# PCB-JOY-RCP_x.net
KiCad netlist of a schematic drawn in EAGLE
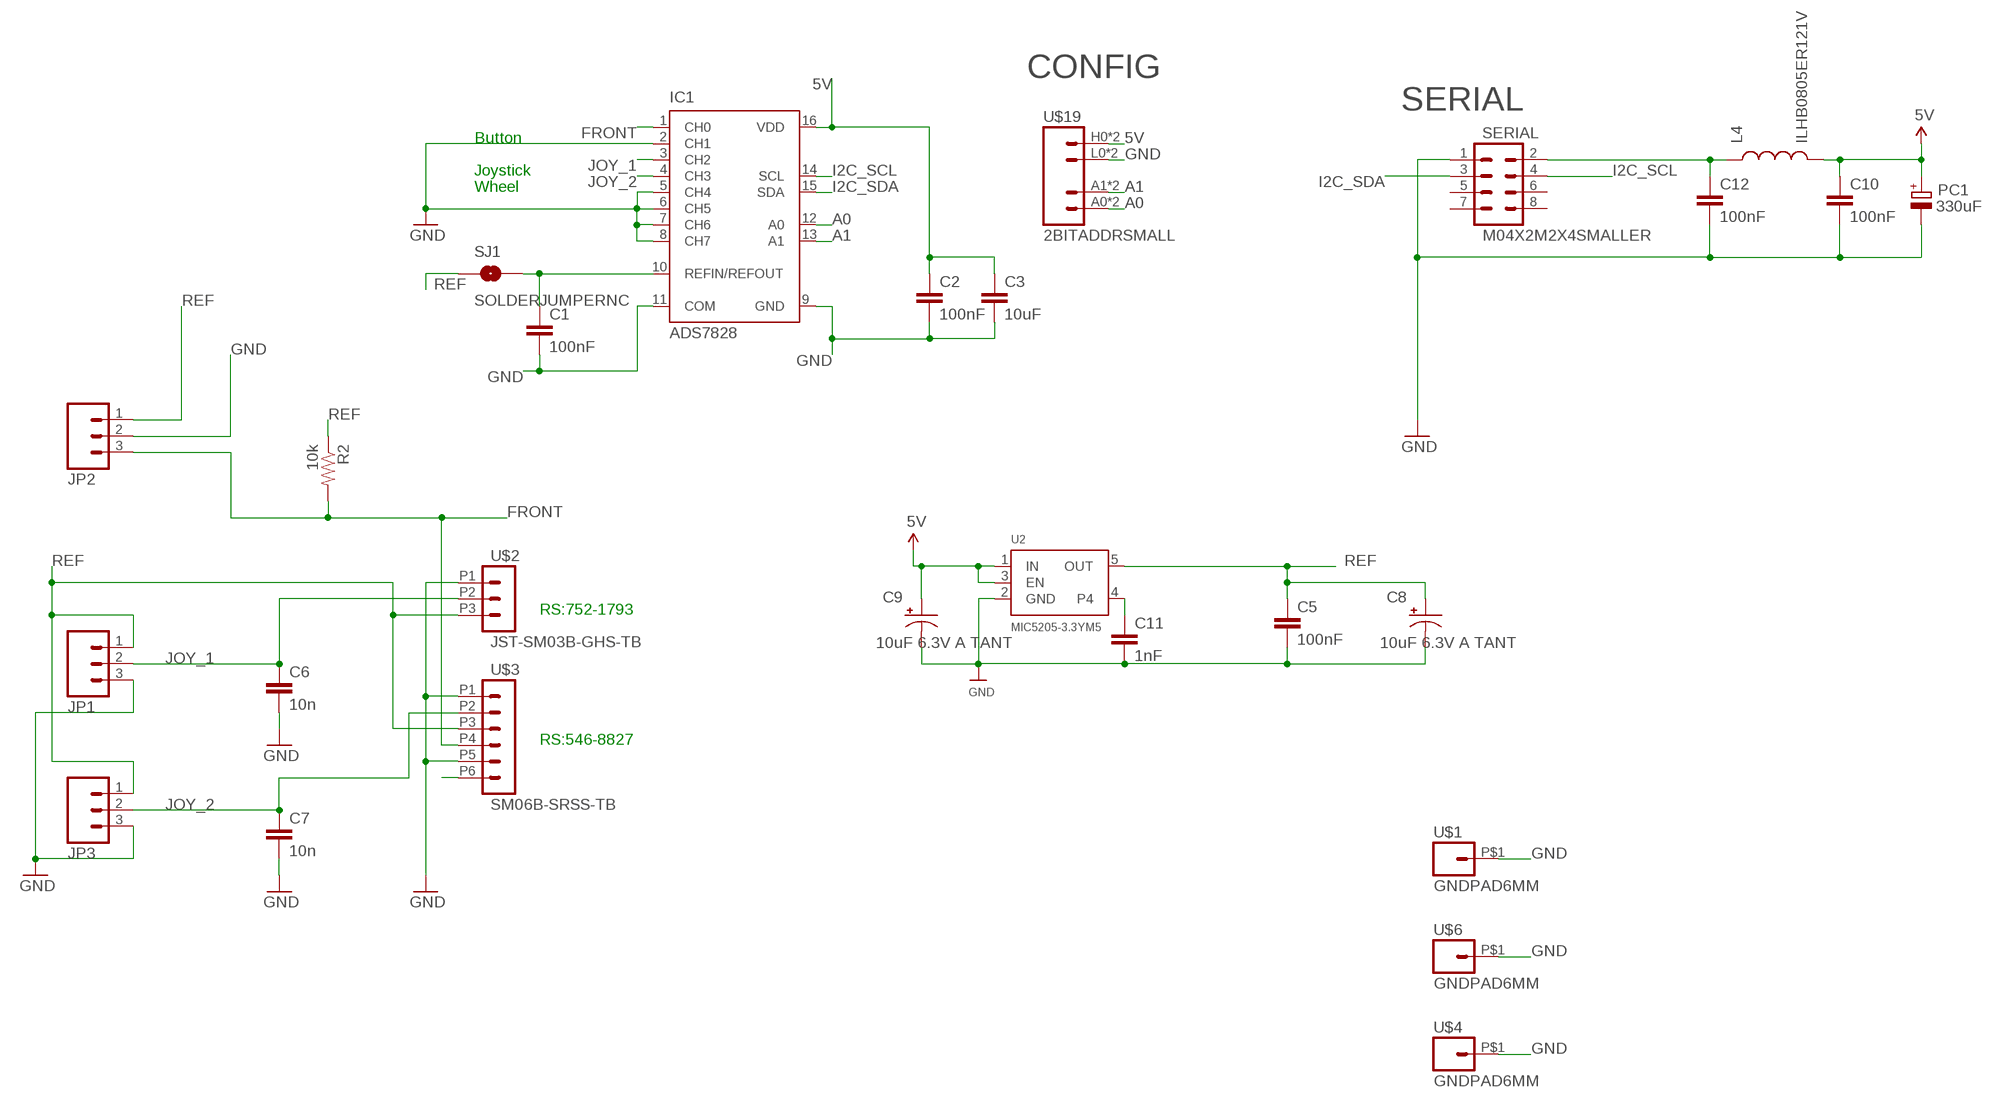
[diagram p0: schematic, sheet 1]

(export (version "E")
  (design (tool "Eeschema 10.0.6"))
  (components
    (comp (ref "C1")
      (value "100nF")
      (footprint "eagle-import:0603-CAP")
      (libsource (lib "eagle-import") (part "CAP0603-CAP"))
    )
    (comp (ref "C2")
      (value "100nF")
      (footprint "eagle-import:0603-CAP")
      (libsource (lib "eagle-import") (part "CAP0603-CAP"))
    )
    (comp (ref "C3")
      (value "10uF")
      (footprint "eagle-import:0805")
      (libsource (lib "eagle-import") (part "CAP0805"))
    )
    (comp (ref "C5")
      (value "100nF")
      (footprint "eagle-import:0603-CAP")
      (libsource (lib "eagle-import") (part "CAP0603-CAP"))
    )
    (comp (ref "C6")
      (value "10n")
      (footprint "eagle-import:0603-CAP")
      (libsource (lib "eagle-import") (part "CAP0603-CAP"))
    )
    (comp (ref "C7")
      (value "10n")
      (footprint "eagle-import:0603-CAP")
      (libsource (lib "eagle-import") (part "CAP0603-CAP"))
    )
    (comp (ref "C8")
      (value "10uF 6.3V A TANT")
      (footprint "eagle-import:EIA3216")
      (libsource (lib "eagle-import") (part "CAP_POL1206"))
    )
    (comp (ref "C9")
      (value "10uF 6.3V A TANT")
      (footprint "eagle-import:EIA3216")
      (libsource (lib "eagle-import") (part "CAP_POL1206"))
    )
    (comp (ref "C10")
      (value "100nF")
      (footprint "eagle-import:0603-CAP")
      (libsource (lib "eagle-import") (part "CAP0603-CAP"))
    )
    (comp (ref "C11")
      (value "1nF")
      (footprint "eagle-import:0603-CAP")
      (libsource (lib "eagle-import") (part "CAP0603-CAP"))
    )
    (comp (ref "C12")
      (value "100nF")
      (footprint "eagle-import:0603-CAP")
      (libsource (lib "eagle-import") (part "CAP0603-CAP"))
    )
    (comp (ref "IC1")
      (value "ADS7828")
      (footprint "eagle-import:TSSOP16-PW")
      (fields (field (name "MF") "TEXAS INSTRUMENTS") (field (name "MPN") "ADS7828E/250"))
      (libsource (lib "eagle-import") (part "ADS7828"))
    )
    (comp (ref "JP1")
      (value "M03PTH")
      (footprint "eagle-import:1X03")
      (libsource (lib "eagle-import") (part "M03PTH"))
    )
    (comp (ref "JP2")
      (value "M03PTH")
      (footprint "eagle-import:1X03")
      (libsource (lib "eagle-import") (part "M03PTH"))
    )
    (comp (ref "JP3")
      (value "M03PTH")
      (footprint "eagle-import:1X03")
      (libsource (lib "eagle-import") (part "M03PTH"))
    )
    (comp (ref "L4")
      (value "ILHB0805ER121V")
      (footprint "eagle-import:0805")
      (libsource (lib "eagle-import") (part "INDUCTOR0805"))
    )
    (comp (ref "PC1")
      (value "330uF")
      (footprint "eagle-import:PANASONIC_D")
      (libsource (lib "eagle-import") (part "CPOL-EUD"))
    )
    (comp (ref "R2")
      (value "10k")
      (footprint "eagle-import:0603-RES")
      (libsource (lib "eagle-import") (part "RESISTOR0603-RES"))
    )
    (comp (ref "SERIAL")
      (value "M04X2M2X4SMALLER")
      (footprint "eagle-import:M2X4SMALLER")
      (libsource (lib "eagle-import") (part "M04X2M2X4SMALLER"))
    )
    (comp (ref "SJ1")
      (value "SOLDERJUMPERNC")
      (footprint "eagle-import:SJ_2S")
      (libsource (lib "eagle-import") (part "SOLDERJUMPERNC"))
    )
    (comp (ref "U$1")
      (value "GNDPAD6MM")
      (footprint "eagle-import:3.2MMPAD6MM")
      (libsource (lib "eagle-import") (part "GNDPAD6MM"))
    )
    (comp (ref "U$2")
      (value "JST-SM03B-GHS-TB")
      (footprint "eagle-import:JST-SM03B-GHS-TB")
      (libsource (lib "eagle-import") (part "JST-SM03B-GHS-TB"))
    )
    (comp (ref "U$3")
      (value "SM06B-SRSS-TB")
      (footprint "eagle-import:JST-SM06B-SRSS-TB")
      (libsource (lib "eagle-import") (part "SM06B-SRSS-TB"))
    )
    (comp (ref "U$4")
      (value "GNDPAD6MM")
      (footprint "eagle-import:3.2MMPAD6MM")
      (libsource (lib "eagle-import") (part "GNDPAD6MM"))
    )
    (comp (ref "U$6")
      (value "GNDPAD6MM")
      (footprint "eagle-import:3.2MMPAD6MM")
      (libsource (lib "eagle-import") (part "GNDPAD6MM"))
    )
    (comp (ref "U$19")
      (value "2BITADDRSMALL")
      (footprint "eagle-import:2BITADDR_SMALL")
      (libsource (lib "eagle-import") (part "2BITADDRSMALL"))
    )
    (comp (ref "U2")
      (value "MIC5205-3.3YM5")
      (footprint "eagle-import:SOT23-5")
      (libsource (lib "eagle-import") (part "VREG_SOT23-5"))
    )
  )
  (nets
    (net (code "1") (name "/A0") (class "Default")
      (node (ref "IC1") (pin "12") (pinfunction "A0_12") (pintype "input"))
      (node (ref "U$19") (pin "A0") (pinfunction "A1_A0") (pintype "passive"))
      (node (ref "U$19") (pin "AS0") (pinfunction "A1_AS0") (pintype "passive"))
    )
    (net (code "2") (name "/A1") (class "Default")
      (node (ref "IC1") (pin "13") (pinfunction "A1_13") (pintype "input"))
      (node (ref "U$19") (pin "A1") (pinfunction "A2_A1") (pintype "passive"))
      (node (ref "U$19") (pin "AS1") (pinfunction "A2_AS1") (pintype "passive"))
    )
    (net (code "3") (name "/FRONT") (class "Default")
      (node (ref "IC1") (pin "1") (pinfunction "CH0_1") (pintype "input"))
      (node (ref "JP2") (pin "3") (pinfunction "3_3") (pintype "passive"))
      (node (ref "R2") (pin "2") (pinfunction "2_2") (pintype "passive"))
      (node (ref "U$3") (pin "P4") (pinfunction "4_P4") (pintype "passive"))
    )
    (net (code "4") (name "/I2C_SCL") (class "Default")
      (node (ref "IC1") (pin "14") (pinfunction "SCL_14") (pintype "input"))
      (node (ref "SERIAL") (pin "4") (pinfunction "4_4") (pintype "passive"))
    )
    (net (code "5") (name "/I2C_SDA") (class "Default")
      (node (ref "IC1") (pin "15") (pinfunction "SDA_15") (pintype "bidirectional"))
      (node (ref "SERIAL") (pin "3") (pinfunction "3_3") (pintype "passive"))
    )
    (net (code "6") (name "/JOY_1") (class "Default")
      (node (ref "C6") (pin "1") (pinfunction "1_1") (pintype "passive"))
      (node (ref "IC1") (pin "3") (pinfunction "CH2_3") (pintype "input"))
      (node (ref "JP1") (pin "2") (pinfunction "2_2") (pintype "passive"))
      (node (ref "U$2") (pin "P2") (pinfunction "2_P2") (pintype "passive"))
    )
    (net (code "7") (name "/JOY_2") (class "Default")
      (node (ref "C7") (pin "1") (pinfunction "1_1") (pintype "passive"))
      (node (ref "IC1") (pin "4") (pinfunction "CH3_4") (pintype "input"))
      (node (ref "JP3") (pin "2") (pinfunction "2_2") (pintype "passive"))
      (node (ref "U$3") (pin "P2") (pinfunction "2_P2") (pintype "passive"))
    )
    (net (code "8") (name "/REF") (class "Default")
      (node (ref "C5") (pin "1") (pinfunction "1_1") (pintype "passive"))
      (node (ref "C8") (pin "A") (pinfunction "+_A") (pintype "passive"))
      (node (ref "JP1") (pin "1") (pinfunction "1_1") (pintype "passive"))
      (node (ref "JP2") (pin "1") (pinfunction "1_1") (pintype "passive"))
      (node (ref "JP3") (pin "1") (pinfunction "1_1") (pintype "passive"))
      (node (ref "R2") (pin "1") (pinfunction "1_1") (pintype "passive"))
      (node (ref "SJ1") (pin "1") (pinfunction "1_1") (pintype "passive"))
      (node (ref "U$2") (pin "P3") (pinfunction "3_P3") (pintype "passive"))
      (node (ref "U$3") (pin "P3") (pinfunction "3_P3") (pintype "passive"))
      (node (ref "U2") (pin "5") (pinfunction "OUT_5") (pintype "bidirectional"))
    )
    (net (code "9") (name "5V") (class "Default")
      (node (ref "C10") (pin "1") (pinfunction "1_1") (pintype "passive"))
      (node (ref "C2") (pin "1") (pinfunction "1_1") (pintype "passive"))
      (node (ref "C3") (pin "1") (pinfunction "1_1") (pintype "passive"))
      (node (ref "C9") (pin "A") (pinfunction "+_A") (pintype "passive"))
      (node (ref "IC1") (pin "16") (pinfunction "VDD_16") (pintype "power_in"))
      (node (ref "L4") (pin "2") (pinfunction "2_2") (pintype "passive"))
      (node (ref "PC1") (pin "+") (pinfunction "+_+") (pintype "passive"))
      (node (ref "U$19") (pin "H0") (pinfunction "VCC_H0") (pintype "passive"))
      (node (ref "U$19") (pin "H1") (pinfunction "VCC_H1") (pintype "passive"))
      (node (ref "U2") (pin "1") (pinfunction "IN_1") (pintype "bidirectional"))
      (node (ref "U2") (pin "3") (pinfunction "EN_3") (pintype "bidirectional"))
    )
    (net (code "10") (name "GND") (class "Default")
      (node (ref "C1") (pin "2") (pinfunction "2_2") (pintype "passive"))
      (node (ref "C10") (pin "2") (pinfunction "2_2") (pintype "passive"))
      (node (ref "C11") (pin "2") (pinfunction "2_2") (pintype "passive"))
      (node (ref "C12") (pin "2") (pinfunction "2_2") (pintype "passive"))
      (node (ref "C2") (pin "2") (pinfunction "2_2") (pintype "passive"))
      (node (ref "C3") (pin "2") (pinfunction "2_2") (pintype "passive"))
      (node (ref "C5") (pin "2") (pinfunction "2_2") (pintype "passive"))
      (node (ref "C6") (pin "2") (pinfunction "2_2") (pintype "passive"))
      (node (ref "C7") (pin "2") (pinfunction "2_2") (pintype "passive"))
      (node (ref "C8") (pin "C") (pinfunction "-_C") (pintype "passive"))
      (node (ref "C9") (pin "C") (pinfunction "-_C") (pintype "passive"))
      (node (ref "IC1") (pin "11") (pinfunction "COM_11") (pintype "input"))
      (node (ref "IC1") (pin "2") (pinfunction "CH1_2") (pintype "input"))
      (node (ref "IC1") (pin "5") (pinfunction "CH4_5") (pintype "input"))
      (node (ref "IC1") (pin "6") (pinfunction "CH5_6") (pintype "input"))
      (node (ref "IC1") (pin "7") (pinfunction "CH6_7") (pintype "input"))
      (node (ref "IC1") (pin "8") (pinfunction "CH7_8") (pintype "input"))
      (node (ref "IC1") (pin "9") (pinfunction "GND_9") (pintype "power_in"))
      (node (ref "JP1") (pin "3") (pinfunction "3_3") (pintype "passive"))
      (node (ref "JP2") (pin "2") (pinfunction "2_2") (pintype "passive"))
      (node (ref "JP3") (pin "3") (pinfunction "3_3") (pintype "passive"))
      (node (ref "PC1") (pin "-") (pinfunction "-_-") (pintype "passive"))
      (node (ref "SERIAL") (pin "1") (pinfunction "1_1") (pintype "passive"))
      (node (ref "U$1") (pin "P$1") (pinfunction "1_P$1") (pintype "passive"))
      (node (ref "U$19") (pin "L0") (pinfunction "GND_L0") (pintype "passive"))
      (node (ref "U$19") (pin "L1") (pinfunction "GND_L1") (pintype "passive"))
      (node (ref "U$2") (pin "P1") (pinfunction "1_P1") (pintype "passive"))
      (node (ref "U$3") (pin "P1") (pinfunction "1_P1") (pintype "passive"))
      (node (ref "U$3") (pin "P5") (pinfunction "5_P5") (pintype "passive"))
      (node (ref "U$4") (pin "P$1") (pinfunction "1_P$1") (pintype "passive"))
      (node (ref "U$6") (pin "P$1") (pinfunction "1_P$1") (pintype "passive"))
      (node (ref "U2") (pin "2") (pinfunction "GND_2") (pintype "bidirectional"))
    )
    (net (code "11") (name "Net-(C12-Pad1)") (class "Default")
      (node (ref "C12") (pin "1") (pinfunction "1_1") (pintype "passive"))
      (node (ref "L4") (pin "1") (pinfunction "1_1") (pintype "passive"))
      (node (ref "SERIAL") (pin "2") (pinfunction "2_2") (pintype "passive"))
    )
    (net (code "12") (name "Net-(IC1-REFIN{slash}REFOUT)") (class "Default")
      (node (ref "C1") (pin "1") (pinfunction "1_1") (pintype "passive"))
      (node (ref "IC1") (pin "10") (pinfunction "REFIN/REFOUT_10") (pintype "passive"))
      (node (ref "SJ1") (pin "2") (pinfunction "2_2") (pintype "passive"))
    )
    (net (code "13") (name "Net-(U2-P4)") (class "Default")
      (node (ref "C11") (pin "1") (pinfunction "1_1") (pintype "passive"))
      (node (ref "U2") (pin "4") (pinfunction "P4_4") (pintype "bidirectional"))
    )
    (net (code "14") (name "unconnected-(SERIAL-Pad5)") (class "Default")
      (node (ref "SERIAL") (pin "5") (pinfunction "5_5") (pintype "passive"))
    )
    (net (code "15") (name "unconnected-(SERIAL-Pad6)") (class "Default")
      (node (ref "SERIAL") (pin "6") (pinfunction "6_6") (pintype "passive"))
    )
    (net (code "16") (name "unconnected-(SERIAL-Pad7)") (class "Default")
      (node (ref "SERIAL") (pin "7") (pinfunction "7_7") (pintype "passive"))
    )
    (net (code "17") (name "unconnected-(SERIAL-Pad8)") (class "Default")
      (node (ref "SERIAL") (pin "8") (pinfunction "8_8") (pintype "passive"))
    )
    (net (code "18") (name "unconnected-(U$3-6-PadP6)") (class "Default")
      (node (ref "U$3") (pin "P6") (pinfunction "6_P6") (pintype "passive"))
    )
  )
)
